# 467444_130_3_4-R1.net
KiCad netlist of a schematic drawn in Altium Designer
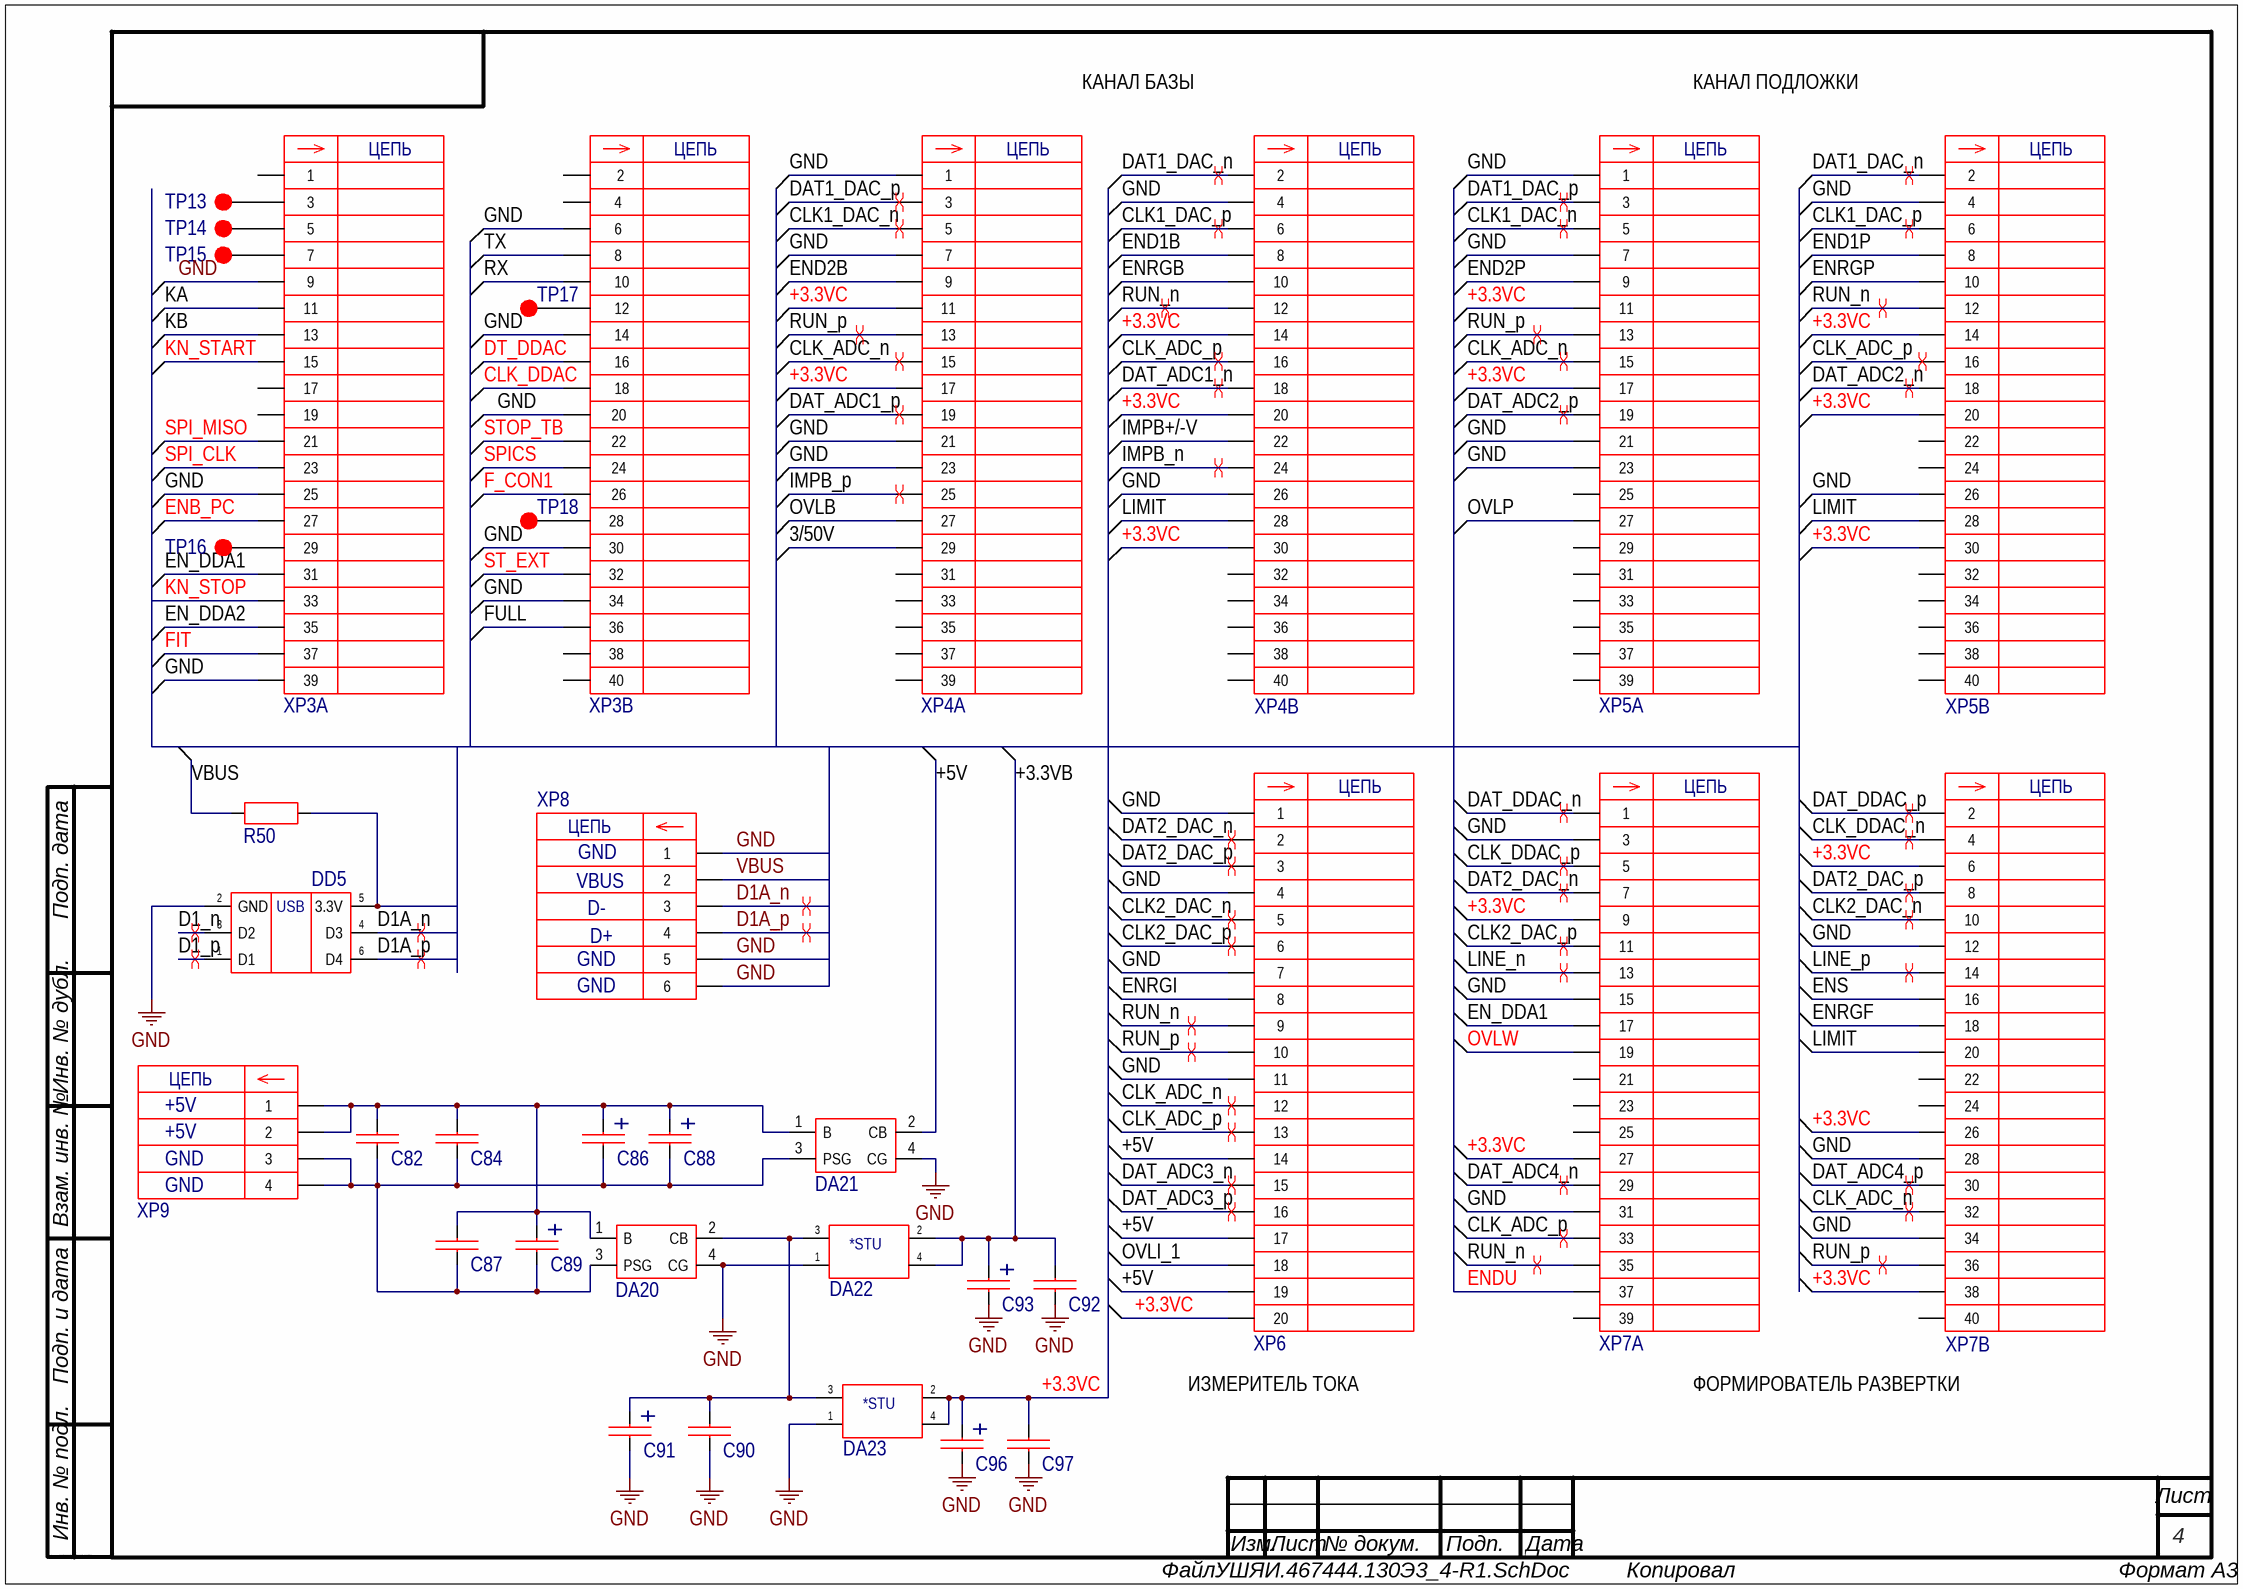
[diagram p0: УШЯИ.467444.130Э3_4-R1.SchDoc]

(export (version "E")
  (design (tool "Eeschema 10.0.6"))
  (components
    (comp (ref "C82")
      (value "0,1 µF")
      (footprint "C_0805 [2012 Metric]")
      (description "Неполярный конденсатор")
      (fields (field (name "MANUFACTURER") "Murata") (field (name "VOLTAGE") "50V"))
      (libsource (lib "lib") (part "C_const"))
    )
    (comp (ref "C84")
      (value "0,1 µF")
      (footprint "C_0805 [2012 Metric]")
      (description "Неполярный конденсатор")
      (fields (field (name "MANUFACTURER") "Murata") (field (name "VOLTAGE") "50V"))
      (libsource (lib "lib") (part "C_const"))
    )
    (comp (ref "C86")
      (value "1000 µF")
      (footprint "С_EXR_10x21")
      (description "Полярный конденсатор")
      (fields (field (name "MANUFACTURER") "Hitano") (field (name "VOLTAGE") "16V"))
      (libsource (lib "lib") (part "C_electrolytic"))
    )
    (comp (ref "C87")
      (value "0,1 µF")
      (footprint "C_0805 [2012 Metric]")
      (description "Неполярный конденсатор")
      (fields (field (name "MANUFACTURER") "Murata") (field (name "VOLTAGE") "50V"))
      (libsource (lib "lib") (part "C_const"))
    )
    (comp (ref "C88")
      (value "10 µF")
      (footprint "C+_1210 [3528-21 Metric]")
      (description "Полярный конденсатор")
      (fields (field (name "MANUFACTURER") "KYOCERA AVX") (field (name "VOLTAGE") "20V\r\n10V"))
      (libsource (lib "lib") (part "C_electrolytic"))
    )
    (comp (ref "C89")
      (value "10 µF")
      (footprint "C+_1210 [3528-21 Metric]")
      (description "Полярный конденсатор")
      (fields (field (name "MANUFACTURER") "KYOCERA AVX") (field (name "VOLTAGE") "20V\r\n10V"))
      (libsource (lib "lib") (part "C_electrolytic"))
    )
    (comp (ref "C90")
      (value "0,1 µF")
      (footprint "C_0805 [2012 Metric]")
      (description "Неполярный конденсатор")
      (fields (field (name "MANUFACTURER") "Murata") (field (name "VOLTAGE") "50V"))
      (libsource (lib "lib") (part "C_const"))
    )
    (comp (ref "C91")
      (value "10 µF")
      (footprint "C+_1210 [3528-21 Metric]")
      (description "Полярный конденсатор")
      (fields (field (name "MANUFACTURER") "KYOCERA AVX") (field (name "VOLTAGE") "20V\r\n10V"))
      (libsource (lib "lib") (part "C_electrolytic"))
    )
    (comp (ref "C92")
      (value "~")
      (footprint "C_0805 [2012 Metric]")
      (description "Неполярный конденсатор")
      (fields (field (name "MANUFACTURER") "Murata") (field (name "VOLTAGE") "50V"))
      (libsource (lib "lib") (part "C_const"))
    )
    (comp (ref "C93")
      (value "~")
      (footprint "C+_1210 [3528-21 Metric]")
      (description "Полярный конденсатор")
      (fields (field (name "MANUFACTURER") "KYOCERA AVX") (field (name "VOLTAGE") "20V\r\n10V"))
      (libsource (lib "lib") (part "C_electrolytic"))
    )
    (comp (ref "C96")
      (value "~")
      (footprint "C+_1210 [3528-21 Metric]")
      (description "Полярный конденсатор")
      (fields (field (name "MANUFACTURER") "KYOCERA AVX") (field (name "VOLTAGE") "20V\r\n10V"))
      (libsource (lib "lib") (part "C_electrolytic"))
    )
    (comp (ref "C97")
      (value "~")
      (footprint "C_0805 [2012 Metric]")
      (description "Неполярный конденсатор")
      (fields (field (name "MANUFACTURER") "Murata") (field (name "VOLTAGE") "50V"))
      (libsource (lib "lib") (part "C_const"))
    )
    (comp (ref "DA20")
      (value "BNX028-01")
      (footprint "F_BNX028-01")
      (description "16В, 35дБ")
      (fields (field (name "MANUFACTURER") "Murata Electronics"))
      (libsource (lib "lib") (part "F_BNX022-01"))
    )
    (comp (ref "DA21")
      (value "BNX028-01")
      (footprint "F_BNX028-01")
      (description "16В, 35дБ")
      (fields (field (name "MANUFACTURER") "Murata Electronics"))
      (libsource (lib "lib") (part "F_BNX022-01"))
    )
    (comp (ref "DA22")
      (value "LD1117AS33TR")
      (footprint "SOT-223")
      (description "IC, Fixed LDO Voltage Regulator, 5.3V to 10V, 1.15V Dropout, 3.3Vout, 1Aout")
      (fields (field (name "MANUFACTURER") "STMicroelectronics"))
      (libsource (lib "lib") (part "VolReg_LD1117AS33TR"))
    )
    (comp (ref "DA23")
      (value "LD1117AS33TR")
      (footprint "SOT-223")
      (description "IC, Fixed LDO Voltage Regulator, 5.3V to 10V, 1.15V Dropout, 3.3Vout, 1Aout")
      (fields (field (name "MANUFACTURER") "STMicroelectronics"))
      (libsource (lib "lib") (part "VolReg_LD1117AS33TR"))
    )
    (comp (ref "DD5")
      (value "USBUF01W6")
      (footprint "SOT-323-6")
      (description "EMI Filter, 2-Channel, USB Upstream Terminator, ESD Protection")
      (fields (field (name "MANUFACTURER") "STMicroelectronics"))
      (libsource (lib "lib") (part "USBUF01W6"))
    )
    (comp (ref "R50")
      (value "30R")
      (footprint "R_0805 [2012 Metric]")
      (fields (field (name "TOLERANCE") "±5%"))
      (libsource (lib "lib") (part "R_Const"))
    )
    (comp (ref "TP13") (value "~") (footprint "DSP_1.3") (libsource (lib "lib") (part "TP")))
    (comp (ref "TP14") (value "~") (footprint "DSP_1.3") (libsource (lib "lib") (part "TP")))
    (comp (ref "TP15") (value "~") (footprint "DSP_1.3") (libsource (lib "lib") (part "TP")))
    (comp (ref "TP16") (value "~") (footprint "DSP_1.3") (libsource (lib "lib") (part "TP")))
    (comp (ref "TP17") (value "~") (footprint "DSP_1.3") (libsource (lib "lib") (part "TP")))
    (comp (ref "TP18") (value "~") (footprint "DSP_1.3") (libsource (lib "lib") (part "TP")))
    (comp (ref "XP3")
      (value "BH-40")
      (footprint "BH-40")
      (description "Male, 40 pins, 2 rows, Vertical, DS1013-40S, 2.54 mm")
      (fields (field (name "MANUFACTURER") "Connfly electronic"))
      (libsource (lib "") (part "M_40_1"))
    )
    (comp (ref "XP4")
      (value "BH2-40")
      (footprint "BH2-40")
      (description "Male, 40 pins, 2 rows, Vertical, DS1014-40, 2 mm")
      (fields (field (name "MANUFACTURER") "Connfly electronic"))
      (libsource (lib "lib") (part "M_40"))
    )
    (comp (ref "XP5")
      (value "BH2-40")
      (footprint "BH2-40")
      (description "Male, 40 pins, 2 rows, Vertical, DS1014-40, 2 mm")
      (fields (field (name "MANUFACTURER") "Connfly electronic"))
      (libsource (lib "lib") (part "M_40"))
    )
    (comp (ref "XP6")
      (value "BH2-20R")
      (footprint "BH2-20R")
      (description "Male, 20 pins, 2 rows, Right Angle, DS1014-20RF1B-B, 2 mm")
      (fields (field (name "MANUFACTURER") "Connfly electronic"))
      (libsource (lib "lib") (part "M_20"))
    )
    (comp (ref "XP7")
      (value "BH2-40")
      (footprint "BH2-40")
      (description "Male, 40 pins, 2 rows, Vertical, DS1014-40, 2 mm")
      (fields (field (name "MANUFACTURER") "Connfly electronic"))
      (libsource (lib "lib") (part "M_40"))
    )
    (comp (ref "XP8")
      (value "AMPMODU II 280372-2")
      (footprint "AMP II-280372-2")
      (description "Male, 6 pin, 1 row, Vertical, Board-to-Board, 2.54 mm")
      (fields (field (name "MANUFACTURER") "TE Connectivity"))
      (libsource (lib "lib") (part "M_6"))
    )
    (comp (ref "XP9")
      (value "AMPMODU II 280371-2")
      (footprint "AMP II-280371-2")
      (description "Male, 4 pin, 1 row, Vertical, Board-to-Board, 2.54 mm")
      (fields (field (name "MANUFACTURER") "TE Connectivity"))
      (libsource (lib "lib") (part "M_4"))
    )
  )
  (nets
    (net (code "1") (name "/+3.3VB") (class "Default")
      (node (ref "C92") (pin "2") (pinfunction "2_2") (pintype "passive"))
      (node (ref "C93") (pin "+") (pinfunction "+_+") (pintype "passive"))
      (node (ref "DA22") (pin "2") (pinfunction "VOUT_2") (pintype "passive"))
      (node (ref "DA22") (pin "4") (pinfunction "VOUT_4") (pintype "passive"))
    )
    (net (code "2") (name "/+3.3VC") (class "Default")
      (node (ref "C96") (pin "+") (pinfunction "+_+") (pintype "passive"))
      (node (ref "C97") (pin "2") (pinfunction "2_2") (pintype "passive"))
      (node (ref "DA23") (pin "2") (pinfunction "VOUT_2") (pintype "passive"))
      (node (ref "DA23") (pin "4") (pinfunction "VOUT_4") (pintype "passive"))
      (node (ref "XP4") (pin "11") (pinfunction "11_11") (pintype "passive"))
      (node (ref "XP4") (pin "14") (pinfunction "14_14") (pintype "passive"))
      (node (ref "XP4") (pin "17") (pinfunction "17_17") (pintype "passive"))
      (node (ref "XP4") (pin "20") (pinfunction "20_20") (pintype "passive"))
      (node (ref "XP4") (pin "30") (pinfunction "30_30") (pintype "passive"))
      (node (ref "XP5") (pin "11") (pinfunction "11_11") (pintype "passive"))
      (node (ref "XP5") (pin "14") (pinfunction "14_14") (pintype "passive"))
      (node (ref "XP5") (pin "17") (pinfunction "17_17") (pintype "passive"))
      (node (ref "XP5") (pin "20") (pinfunction "20_20") (pintype "passive"))
      (node (ref "XP5") (pin "30") (pinfunction "30_30") (pintype "passive"))
      (node (ref "XP6") (pin "20") (pinfunction "20_20") (pintype "passive"))
      (node (ref "XP7") (pin "26") (pinfunction "26_26") (pintype "passive"))
      (node (ref "XP7") (pin "27") (pinfunction "27_27") (pintype "passive"))
      (node (ref "XP7") (pin "38") (pinfunction "38_38") (pintype "passive"))
      (node (ref "XP7") (pin "6") (pinfunction "6_6") (pintype "passive"))
      (node (ref "XP7") (pin "9") (pinfunction "9_9") (pintype "passive"))
    )
    (net (code "3") (name "/+5V") (class "Default")
      (node (ref "DA21") (pin "2") (pinfunction "CB_2") (pintype "passive"))
      (node (ref "XP6") (pin "14") (pinfunction "14_14") (pintype "passive"))
      (node (ref "XP6") (pin "17") (pinfunction "17_17") (pintype "passive"))
      (node (ref "XP6") (pin "19") (pinfunction "19_19") (pintype "passive"))
    )
    (net (code "4") (name "/3{slash}50V") (class "Default")
      (node (ref "XP4") (pin "29") (pinfunction "29_29") (pintype "passive"))
    )
    (net (code "5") (name "/CLK1_DAC_n") (class "Default")
      (node (ref "XP4") (pin "5") (pinfunction "5_5") (pintype "passive"))
      (node (ref "XP5") (pin "5") (pinfunction "5_5") (pintype "passive"))
    )
    (net (code "6") (name "/CLK1_DAC_p") (class "Default")
      (node (ref "XP4") (pin "6") (pinfunction "6_6") (pintype "passive"))
      (node (ref "XP5") (pin "6") (pinfunction "6_6") (pintype "passive"))
    )
    (net (code "7") (name "/CLK2_DAC_n") (class "Default")
      (node (ref "XP6") (pin "5") (pinfunction "5_5") (pintype "passive"))
      (node (ref "XP7") (pin "10") (pinfunction "10_10") (pintype "passive"))
    )
    (net (code "8") (name "/CLK2_DAC_p") (class "Default")
      (node (ref "XP6") (pin "6") (pinfunction "6_6") (pintype "passive"))
      (node (ref "XP7") (pin "11") (pinfunction "11_11") (pintype "passive"))
    )
    (net (code "9") (name "/CLK_ADC_n") (class "Default")
      (node (ref "XP4") (pin "15") (pinfunction "15_15") (pintype "passive"))
      (node (ref "XP5") (pin "15") (pinfunction "15_15") (pintype "passive"))
      (node (ref "XP6") (pin "12") (pinfunction "12_12") (pintype "passive"))
      (node (ref "XP7") (pin "32") (pinfunction "32_32") (pintype "passive"))
    )
    (net (code "10") (name "/CLK_ADC_p") (class "Default")
      (node (ref "XP4") (pin "16") (pinfunction "16_16") (pintype "passive"))
      (node (ref "XP5") (pin "16") (pinfunction "16_16") (pintype "passive"))
      (node (ref "XP6") (pin "13") (pinfunction "13_13") (pintype "passive"))
      (node (ref "XP7") (pin "33") (pinfunction "33_33") (pintype "passive"))
    )
    (net (code "11") (name "/CLK_DDAC") (class "Default")
      (node (ref "XP3") (pin "18") (pinfunction "18_18") (pintype "passive"))
    )
    (net (code "12") (name "/CLK_DDAC_n") (class "Default")
      (node (ref "XP7") (pin "4") (pinfunction "4_4") (pintype "passive"))
    )
    (net (code "13") (name "/CLK_DDAC_p") (class "Default")
      (node (ref "XP7") (pin "5") (pinfunction "5_5") (pintype "passive"))
    )
    (net (code "14") (name "/D1A_n") (class "Default")
      (node (ref "DD5") (pin "4") (pinfunction "D3_4") (pintype "passive"))
      (node (ref "XP8") (pin "3") (pinfunction "3_3") (pintype "passive"))
    )
    (net (code "15") (name "/D1A_p") (class "Default")
      (node (ref "DD5") (pin "6") (pinfunction "D4_6") (pintype "passive"))
      (node (ref "XP8") (pin "4") (pinfunction "4_4") (pintype "passive"))
    )
    (net (code "16") (name "/D1_n") (class "Default")
      (node (ref "DD5") (pin "3") (pinfunction "D2_3") (pintype "passive"))
    )
    (net (code "17") (name "/D1_p") (class "Default")
      (node (ref "DD5") (pin "1") (pinfunction "D1_1") (pintype "passive"))
    )
    (net (code "18") (name "/DAT1_DAC_n") (class "Default")
      (node (ref "XP4") (pin "2") (pinfunction "2_2") (pintype "passive"))
      (node (ref "XP5") (pin "2") (pinfunction "2_2") (pintype "passive"))
    )
    (net (code "19") (name "/DAT1_DAC_p") (class "Default")
      (node (ref "XP4") (pin "3") (pinfunction "3_3") (pintype "passive"))
      (node (ref "XP5") (pin "3") (pinfunction "3_3") (pintype "passive"))
    )
    (net (code "20") (name "/DAT2_DAC_n") (class "Default")
      (node (ref "XP6") (pin "2") (pinfunction "2_2") (pintype "passive"))
      (node (ref "XP7") (pin "7") (pinfunction "7_7") (pintype "passive"))
    )
    (net (code "21") (name "/DAT2_DAC_p") (class "Default")
      (node (ref "XP6") (pin "3") (pinfunction "3_3") (pintype "passive"))
      (node (ref "XP7") (pin "8") (pinfunction "8_8") (pintype "passive"))
    )
    (net (code "22") (name "/DAT_ADC1_n") (class "Default")
      (node (ref "XP4") (pin "18") (pinfunction "18_18") (pintype "passive"))
    )
    (net (code "23") (name "/DAT_ADC1_p") (class "Default")
      (node (ref "XP4") (pin "19") (pinfunction "19_19") (pintype "passive"))
    )
    (net (code "24") (name "/DAT_ADC2_n") (class "Default")
      (node (ref "XP5") (pin "18") (pinfunction "18_18") (pintype "passive"))
    )
    (net (code "25") (name "/DAT_ADC2_p") (class "Default")
      (node (ref "XP5") (pin "19") (pinfunction "19_19") (pintype "passive"))
    )
    (net (code "26") (name "/DAT_ADC3_n") (class "Default")
      (node (ref "XP6") (pin "15") (pinfunction "15_15") (pintype "passive"))
    )
    (net (code "27") (name "/DAT_ADC3_p") (class "Default")
      (node (ref "XP6") (pin "16") (pinfunction "16_16") (pintype "passive"))
    )
    (net (code "28") (name "/DAT_ADC4_n") (class "Default")
      (node (ref "XP7") (pin "29") (pinfunction "29_29") (pintype "passive"))
    )
    (net (code "29") (name "/DAT_ADC4_p") (class "Default")
      (node (ref "XP7") (pin "30") (pinfunction "30_30") (pintype "passive"))
    )
    (net (code "30") (name "/DAT_DDAC_n") (class "Default")
      (node (ref "XP7") (pin "1") (pinfunction "1_1") (pintype "passive"))
    )
    (net (code "31") (name "/DAT_DDAC_p") (class "Default")
      (node (ref "XP7") (pin "2") (pinfunction "2_2") (pintype "passive"))
    )
    (net (code "32") (name "/DT_DDAC") (class "Default")
      (node (ref "XP3") (pin "16") (pinfunction "16_16") (pintype "passive"))
    )
    (net (code "33") (name "/ENB_PC") (class "Default")
      (node (ref "XP3") (pin "27") (pinfunction "27_27") (pintype "passive"))
    )
    (net (code "34") (name "/END1B") (class "Default")
      (node (ref "XP4") (pin "8") (pinfunction "8_8") (pintype "passive"))
    )
    (net (code "35") (name "/END1P") (class "Default")
      (node (ref "XP5") (pin "8") (pinfunction "8_8") (pintype "passive"))
    )
    (net (code "36") (name "/END2B") (class "Default")
      (node (ref "XP4") (pin "9") (pinfunction "9_9") (pintype "passive"))
    )
    (net (code "37") (name "/END2P") (class "Default")
      (node (ref "XP5") (pin "9") (pinfunction "9_9") (pintype "passive"))
    )
    (net (code "38") (name "/ENDU") (class "Default")
      (node (ref "XP7") (pin "37") (pinfunction "37_37") (pintype "passive"))
    )
    (net (code "39") (name "/ENRGB") (class "Default")
      (node (ref "XP4") (pin "10") (pinfunction "10_10") (pintype "passive"))
    )
    (net (code "40") (name "/ENRGF") (class "Default")
      (node (ref "XP7") (pin "18") (pinfunction "18_18") (pintype "passive"))
    )
    (net (code "41") (name "/ENRGI") (class "Default")
      (node (ref "XP6") (pin "8") (pinfunction "8_8") (pintype "passive"))
    )
    (net (code "42") (name "/ENRGP") (class "Default")
      (node (ref "XP5") (pin "10") (pinfunction "10_10") (pintype "passive"))
    )
    (net (code "43") (name "/ENS") (class "Default")
      (node (ref "XP7") (pin "16") (pinfunction "16_16") (pintype "passive"))
    )
    (net (code "44") (name "/EN_DDA1") (class "Default")
      (node (ref "XP3") (pin "31") (pinfunction "31_31") (pintype "passive"))
      (node (ref "XP7") (pin "17") (pinfunction "17_17") (pintype "passive"))
    )
    (net (code "45") (name "/EN_DDA2") (class "Default")
      (node (ref "XP3") (pin "35") (pinfunction "35_35") (pintype "passive"))
    )
    (net (code "46") (name "/FIT") (class "Default")
      (node (ref "XP3") (pin "37") (pinfunction "37_37") (pintype "passive"))
    )
    (net (code "47") (name "/FULL") (class "Default")
      (node (ref "XP3") (pin "36") (pinfunction "36_36") (pintype "passive"))
    )
    (net (code "48") (name "/F_CON1") (class "Default")
      (node (ref "XP3") (pin "26") (pinfunction "26_26") (pintype "passive"))
    )
    (net (code "49") (name "/IMPB+{slash}-V") (class "Default")
      (node (ref "XP4") (pin "22") (pinfunction "22_22") (pintype "passive"))
    )
    (net (code "50") (name "/IMPB_n") (class "Default")
      (node (ref "XP4") (pin "24") (pinfunction "24_24") (pintype "passive"))
    )
    (net (code "51") (name "/IMPB_p") (class "Default")
      (node (ref "XP4") (pin "25") (pinfunction "25_25") (pintype "passive"))
    )
    (net (code "52") (name "/KA") (class "Default")
      (node (ref "XP3") (pin "11") (pinfunction "11_11") (pintype "passive"))
    )
    (net (code "53") (name "/KB") (class "Default")
      (node (ref "XP3") (pin "13") (pinfunction "13_13") (pintype "passive"))
    )
    (net (code "54") (name "/KN_START") (class "Default")
      (node (ref "XP3") (pin "15") (pinfunction "15_15") (pintype "passive"))
    )
    (net (code "55") (name "/KN_STOP") (class "Default")
      (node (ref "XP3") (pin "33") (pinfunction "33_33") (pintype "passive"))
    )
    (net (code "56") (name "/LIMIT") (class "Default")
      (node (ref "XP4") (pin "28") (pinfunction "28_28") (pintype "passive"))
      (node (ref "XP5") (pin "28") (pinfunction "28_28") (pintype "passive"))
      (node (ref "XP7") (pin "20") (pinfunction "20_20") (pintype "passive"))
    )
    (net (code "57") (name "/LINE_n") (class "Default")
      (node (ref "XP7") (pin "13") (pinfunction "13_13") (pintype "passive"))
    )
    (net (code "58") (name "/LINE_p") (class "Default")
      (node (ref "XP7") (pin "14") (pinfunction "14_14") (pintype "passive"))
    )
    (net (code "59") (name "/OVLB") (class "Default")
      (node (ref "XP4") (pin "27") (pinfunction "27_27") (pintype "passive"))
    )
    (net (code "60") (name "/OVLI_1") (class "Default")
      (node (ref "XP6") (pin "18") (pinfunction "18_18") (pintype "passive"))
    )
    (net (code "61") (name "/OVLP") (class "Default")
      (node (ref "XP5") (pin "27") (pinfunction "27_27") (pintype "passive"))
    )
    (net (code "62") (name "/OVLW") (class "Default")
      (node (ref "XP7") (pin "19") (pinfunction "19_19") (pintype "passive"))
    )
    (net (code "63") (name "/RUN_n") (class "Default")
      (node (ref "XP4") (pin "12") (pinfunction "12_12") (pintype "passive"))
      (node (ref "XP5") (pin "12") (pinfunction "12_12") (pintype "passive"))
      (node (ref "XP6") (pin "9") (pinfunction "9_9") (pintype "passive"))
      (node (ref "XP7") (pin "35") (pinfunction "35_35") (pintype "passive"))
    )
    (net (code "64") (name "/RUN_p") (class "Default")
      (node (ref "XP4") (pin "13") (pinfunction "13_13") (pintype "passive"))
      (node (ref "XP5") (pin "13") (pinfunction "13_13") (pintype "passive"))
      (node (ref "XP6") (pin "10") (pinfunction "10_10") (pintype "passive"))
      (node (ref "XP7") (pin "36") (pinfunction "36_36") (pintype "passive"))
    )
    (net (code "65") (name "/RX") (class "Default")
      (node (ref "XP3") (pin "10") (pinfunction "10_10") (pintype "passive"))
    )
    (net (code "66") (name "/SPICS") (class "Default")
      (node (ref "XP3") (pin "24") (pinfunction "24_24") (pintype "passive"))
    )
    (net (code "67") (name "/SPI_CLK") (class "Default")
      (node (ref "XP3") (pin "23") (pinfunction "23_23") (pintype "passive"))
    )
    (net (code "68") (name "/SPI_MISO") (class "Default")
      (node (ref "XP3") (pin "21") (pinfunction "21_21") (pintype "passive"))
    )
    (net (code "69") (name "/STOP_TB") (class "Default")
      (node (ref "XP3") (pin "22") (pinfunction "22_22") (pintype "passive"))
    )
    (net (code "70") (name "/ST_EXT") (class "Default")
      (node (ref "XP3") (pin "32") (pinfunction "32_32") (pintype "passive"))
    )
    (net (code "71") (name "/TX") (class "Default")
      (node (ref "XP3") (pin "8") (pinfunction "8_8") (pintype "passive"))
    )
    (net (code "72") (name "/VBUS") (class "Default")
      (node (ref "R50") (pin "1") (pinfunction "1_1") (pintype "passive"))
      (node (ref "XP8") (pin "2") (pinfunction "2_2") (pintype "passive"))
    )
    (net (code "73") (name "GND") (class "Default")
      (node (ref "C90") (pin "2") (pinfunction "2_2") (pintype "passive"))
      (node (ref "C91") (pin "-") (pinfunction "-_-") (pintype "passive"))
      (node (ref "C92") (pin "1") (pinfunction "1_1") (pintype "passive"))
      (node (ref "C93") (pin "-") (pinfunction "-_-") (pintype "passive"))
      (node (ref "C96") (pin "-") (pinfunction "-_-") (pintype "passive"))
      (node (ref "C97") (pin "1") (pinfunction "1_1") (pintype "passive"))
      (node (ref "DA20") (pin "4") (pinfunction "CG_4") (pintype "passive"))
      (node (ref "DA21") (pin "4") (pinfunction "CG_4") (pintype "passive"))
      (node (ref "DA22") (pin "1") (pinfunction "ADJ/GND_1") (pintype "passive"))
      (node (ref "DA23") (pin "1") (pinfunction "ADJ/GND_1") (pintype "passive"))
      (node (ref "DD5") (pin "2") (pinfunction "GND_2") (pintype "passive"))
      (node (ref "XP3") (pin "14") (pinfunction "14_14") (pintype "passive"))
      (node (ref "XP3") (pin "20") (pinfunction "20_20") (pintype "passive"))
      (node (ref "XP3") (pin "25") (pinfunction "25_25") (pintype "passive"))
      (node (ref "XP3") (pin "30") (pinfunction "30_30") (pintype "passive"))
      (node (ref "XP3") (pin "34") (pinfunction "34_34") (pintype "passive"))
      (node (ref "XP3") (pin "39") (pinfunction "39_39") (pintype "passive"))
      (node (ref "XP3") (pin "6") (pinfunction "6_6") (pintype "passive"))
      (node (ref "XP3") (pin "9") (pinfunction "9_9") (pintype "passive"))
      (node (ref "XP4") (pin "1") (pinfunction "1_1") (pintype "passive"))
      (node (ref "XP4") (pin "21") (pinfunction "21_21") (pintype "passive"))
      (node (ref "XP4") (pin "23") (pinfunction "23_23") (pintype "passive"))
      (node (ref "XP4") (pin "26") (pinfunction "26_26") (pintype "passive"))
      (node (ref "XP4") (pin "4") (pinfunction "4_4") (pintype "passive"))
      (node (ref "XP4") (pin "7") (pinfunction "7_7") (pintype "passive"))
      (node (ref "XP5") (pin "1") (pinfunction "1_1") (pintype "passive"))
      (node (ref "XP5") (pin "21") (pinfunction "21_21") (pintype "passive"))
      (node (ref "XP5") (pin "23") (pinfunction "23_23") (pintype "passive"))
      (node (ref "XP5") (pin "26") (pinfunction "26_26") (pintype "passive"))
      (node (ref "XP5") (pin "4") (pinfunction "4_4") (pintype "passive"))
      (node (ref "XP5") (pin "7") (pinfunction "7_7") (pintype "passive"))
      (node (ref "XP6") (pin "1") (pinfunction "1_1") (pintype "passive"))
      (node (ref "XP6") (pin "11") (pinfunction "11_11") (pintype "passive"))
      (node (ref "XP6") (pin "4") (pinfunction "4_4") (pintype "passive"))
      (node (ref "XP6") (pin "7") (pinfunction "7_7") (pintype "passive"))
      (node (ref "XP7") (pin "12") (pinfunction "12_12") (pintype "passive"))
      (node (ref "XP7") (pin "15") (pinfunction "15_15") (pintype "passive"))
      (node (ref "XP7") (pin "28") (pinfunction "28_28") (pintype "passive"))
      (node (ref "XP7") (pin "3") (pinfunction "3_3") (pintype "passive"))
      (node (ref "XP7") (pin "31") (pinfunction "31_31") (pintype "passive"))
      (node (ref "XP7") (pin "34") (pinfunction "34_34") (pintype "passive"))
      (node (ref "XP8") (pin "1") (pinfunction "1_1") (pintype "passive"))
      (node (ref "XP8") (pin "5") (pinfunction "5_5") (pintype "passive"))
      (node (ref "XP8") (pin "6") (pinfunction "6_6") (pintype "passive"))
    )
    (net (code "74") (name "Net-(DA20-B)") (class "Default")
      (node (ref "C82") (pin "1") (pinfunction "1_1") (pintype "passive"))
      (node (ref "C84") (pin "1") (pinfunction "1_1") (pintype "passive"))
      (node (ref "C86") (pin "+") (pinfunction "+_+") (pintype "passive"))
      (node (ref "C87") (pin "2") (pinfunction "2_2") (pintype "passive"))
      (node (ref "C88") (pin "+") (pinfunction "+_+") (pintype "passive"))
      (node (ref "C89") (pin "+") (pinfunction "+_+") (pintype "passive"))
      (node (ref "DA20") (pin "1") (pinfunction "B_1") (pintype "passive"))
      (node (ref "DA21") (pin "1") (pinfunction "B_1") (pintype "passive"))
      (node (ref "XP9") (pin "1") (pinfunction "1_1") (pintype "passive"))
      (node (ref "XP9") (pin "2") (pinfunction "2_2") (pintype "passive"))
    )
    (net (code "75") (name "Net-(DA20-CB)") (class "Default")
      (node (ref "C90") (pin "1") (pinfunction "1_1") (pintype "passive"))
      (node (ref "C91") (pin "+") (pinfunction "+_+") (pintype "passive"))
      (node (ref "DA20") (pin "2") (pinfunction "CB_2") (pintype "passive"))
      (node (ref "DA22") (pin "3") (pinfunction "VIN_3") (pintype "passive"))
      (node (ref "DA23") (pin "3") (pinfunction "VIN_3") (pintype "passive"))
    )
    (net (code "76") (name "Net-(DA20-PSG)") (class "Default")
      (node (ref "C82") (pin "2") (pinfunction "2_2") (pintype "passive"))
      (node (ref "C84") (pin "2") (pinfunction "2_2") (pintype "passive"))
      (node (ref "C86") (pin "-") (pinfunction "-_-") (pintype "passive"))
      (node (ref "C87") (pin "1") (pinfunction "1_1") (pintype "passive"))
      (node (ref "C88") (pin "-") (pinfunction "-_-") (pintype "passive"))
      (node (ref "C89") (pin "-") (pinfunction "-_-") (pintype "passive"))
      (node (ref "DA20") (pin "3") (pinfunction "PSG_3") (pintype "passive"))
      (node (ref "DA21") (pin "3") (pinfunction "PSG_3") (pintype "passive"))
      (node (ref "XP9") (pin "3") (pinfunction "3_3") (pintype "passive"))
      (node (ref "XP9") (pin "4") (pinfunction "4_4") (pintype "passive"))
    )
    (net (code "77") (name "Net-(DD5-3.3V)") (class "Default")
      (node (ref "DD5") (pin "5") (pinfunction "3.3V_5") (pintype "passive"))
      (node (ref "R50") (pin "2") (pinfunction "2_2") (pintype "passive"))
    )
    (net (code "78") (name "Net-(TP13-Pad1)") (class "Default")
      (node (ref "TP13") (pin "1") (pinfunction "1_1") (pintype "passive"))
      (node (ref "XP3") (pin "3") (pinfunction "3_3") (pintype "passive"))
    )
    (net (code "79") (name "Net-(TP14-Pad1)") (class "Default")
      (node (ref "TP14") (pin "1") (pinfunction "1_1") (pintype "passive"))
      (node (ref "XP3") (pin "5") (pinfunction "5_5") (pintype "passive"))
    )
    (net (code "80") (name "Net-(TP15-Pad1)") (class "Default")
      (node (ref "TP15") (pin "1") (pinfunction "1_1") (pintype "passive"))
      (node (ref "XP3") (pin "7") (pinfunction "7_7") (pintype "passive"))
    )
    (net (code "81") (name "Net-(TP16-Pad1)") (class "Default")
      (node (ref "TP16") (pin "1") (pinfunction "1_1") (pintype "passive"))
      (node (ref "XP3") (pin "29") (pinfunction "29_29") (pintype "passive"))
    )
    (net (code "82") (name "Net-(TP17-Pad1)") (class "Default")
      (node (ref "TP17") (pin "1") (pinfunction "1_1") (pintype "passive"))
      (node (ref "XP3") (pin "12") (pinfunction "12_12") (pintype "passive"))
    )
    (net (code "83") (name "Net-(TP18-Pad1)") (class "Default")
      (node (ref "TP18") (pin "1") (pinfunction "1_1") (pintype "passive"))
      (node (ref "XP3") (pin "28") (pinfunction "28_28") (pintype "passive"))
    )
    (net (code "84") (name "unconnected-(XP3-Pad1)") (class "Default")
      (node (ref "XP3") (pin "1") (pinfunction "1_1") (pintype "passive"))
    )
    (net (code "85") (name "unconnected-(XP3-Pad2)") (class "Default")
      (node (ref "XP3") (pin "2") (pinfunction "2_2") (pintype "passive"))
    )
    (net (code "86") (name "unconnected-(XP3-Pad4)") (class "Default")
      (node (ref "XP3") (pin "4") (pinfunction "4_4") (pintype "passive"))
    )
    (net (code "87") (name "unconnected-(XP3-Pad17)") (class "Default")
      (node (ref "XP3") (pin "17") (pinfunction "17_17") (pintype "passive"))
    )
    (net (code "88") (name "unconnected-(XP3-Pad19)") (class "Default")
      (node (ref "XP3") (pin "19") (pinfunction "19_19") (pintype "passive"))
    )
    (net (code "89") (name "unconnected-(XP3-Pad38)") (class "Default")
      (node (ref "XP3") (pin "38") (pinfunction "38_38") (pintype "passive"))
    )
    (net (code "90") (name "unconnected-(XP3-Pad40)") (class "Default")
      (node (ref "XP3") (pin "40") (pinfunction "40_40") (pintype "passive"))
    )
    (net (code "91") (name "unconnected-(XP4-Pad31)") (class "Default")
      (node (ref "XP4") (pin "31") (pinfunction "31_31") (pintype "passive"))
    )
    (net (code "92") (name "unconnected-(XP4-Pad32)") (class "Default")
      (node (ref "XP4") (pin "32") (pinfunction "32_32") (pintype "passive"))
    )
    (net (code "93") (name "unconnected-(XP4-Pad33)") (class "Default")
      (node (ref "XP4") (pin "33") (pinfunction "33_33") (pintype "passive"))
    )
    (net (code "94") (name "unconnected-(XP4-Pad34)") (class "Default")
      (node (ref "XP4") (pin "34") (pinfunction "34_34") (pintype "passive"))
    )
    (net (code "95") (name "unconnected-(XP4-Pad35)") (class "Default")
      (node (ref "XP4") (pin "35") (pinfunction "35_35") (pintype "passive"))
    )
    (net (code "96") (name "unconnected-(XP4-Pad36)") (class "Default")
      (node (ref "XP4") (pin "36") (pinfunction "36_36") (pintype "passive"))
    )
    (net (code "97") (name "unconnected-(XP4-Pad37)") (class "Default")
      (node (ref "XP4") (pin "37") (pinfunction "37_37") (pintype "passive"))
    )
    (net (code "98") (name "unconnected-(XP4-Pad38)") (class "Default")
      (node (ref "XP4") (pin "38") (pinfunction "38_38") (pintype "passive"))
    )
    (net (code "99") (name "unconnected-(XP4-Pad39)") (class "Default")
      (node (ref "XP4") (pin "39") (pinfunction "39_39") (pintype "passive"))
    )
    (net (code "100") (name "unconnected-(XP4-Pad40)") (class "Default")
      (node (ref "XP4") (pin "40") (pinfunction "40_40") (pintype "passive"))
    )
    (net (code "101") (name "unconnected-(XP5-Pad22)") (class "Default")
      (node (ref "XP5") (pin "22") (pinfunction "22_22") (pintype "passive"))
    )
    (net (code "102") (name "unconnected-(XP5-Pad24)") (class "Default")
      (node (ref "XP5") (pin "24") (pinfunction "24_24") (pintype "passive"))
    )
    (net (code "103") (name "unconnected-(XP5-Pad25)") (class "Default")
      (node (ref "XP5") (pin "25") (pinfunction "25_25") (pintype "passive"))
    )
    (net (code "104") (name "unconnected-(XP5-Pad29)") (class "Default")
      (node (ref "XP5") (pin "29") (pinfunction "29_29") (pintype "passive"))
    )
    (net (code "105") (name "unconnected-(XP5-Pad31)") (class "Default")
      (node (ref "XP5") (pin "31") (pinfunction "31_31") (pintype "passive"))
    )
    (net (code "106") (name "unconnected-(XP5-Pad32)") (class "Default")
      (node (ref "XP5") (pin "32") (pinfunction "32_32") (pintype "passive"))
    )
    (net (code "107") (name "unconnected-(XP5-Pad33)") (class "Default")
      (node (ref "XP5") (pin "33") (pinfunction "33_33") (pintype "passive"))
    )
    (net (code "108") (name "unconnected-(XP5-Pad34)") (class "Default")
      (node (ref "XP5") (pin "34") (pinfunction "34_34") (pintype "passive"))
    )
    (net (code "109") (name "unconnected-(XP5-Pad35)") (class "Default")
      (node (ref "XP5") (pin "35") (pinfunction "35_35") (pintype "passive"))
    )
    (net (code "110") (name "unconnected-(XP5-Pad36)") (class "Default")
      (node (ref "XP5") (pin "36") (pinfunction "36_36") (pintype "passive"))
    )
    (net (code "111") (name "unconnected-(XP5-Pad37)") (class "Default")
      (node (ref "XP5") (pin "37") (pinfunction "37_37") (pintype "passive"))
    )
    (net (code "112") (name "unconnected-(XP5-Pad38)") (class "Default")
      (node (ref "XP5") (pin "38") (pinfunction "38_38") (pintype "passive"))
    )
    (net (code "113") (name "unconnected-(XP5-Pad39)") (class "Default")
      (node (ref "XP5") (pin "39") (pinfunction "39_39") (pintype "passive"))
    )
    (net (code "114") (name "unconnected-(XP5-Pad40)") (class "Default")
      (node (ref "XP5") (pin "40") (pinfunction "40_40") (pintype "passive"))
    )
    (net (code "115") (name "unconnected-(XP7-Pad21)") (class "Default")
      (node (ref "XP7") (pin "21") (pinfunction "21_21") (pintype "passive"))
    )
    (net (code "116") (name "unconnected-(XP7-Pad22)") (class "Default")
      (node (ref "XP7") (pin "22") (pinfunction "22_22") (pintype "passive"))
    )
    (net (code "117") (name "unconnected-(XP7-Pad23)") (class "Default")
      (node (ref "XP7") (pin "23") (pinfunction "23_23") (pintype "passive"))
    )
    (net (code "118") (name "unconnected-(XP7-Pad24)") (class "Default")
      (node (ref "XP7") (pin "24") (pinfunction "24_24") (pintype "passive"))
    )
    (net (code "119") (name "unconnected-(XP7-Pad25)") (class "Default")
      (node (ref "XP7") (pin "25") (pinfunction "25_25") (pintype "passive"))
    )
    (net (code "120") (name "unconnected-(XP7-Pad39)") (class "Default")
      (node (ref "XP7") (pin "39") (pinfunction "39_39") (pintype "passive"))
    )
    (net (code "121") (name "unconnected-(XP7-Pad40)") (class "Default")
      (node (ref "XP7") (pin "40") (pinfunction "40_40") (pintype "passive"))
    )
  )
)
